# Power_MPU.net
KiCad netlist of a schematic drawn in Altium Designer
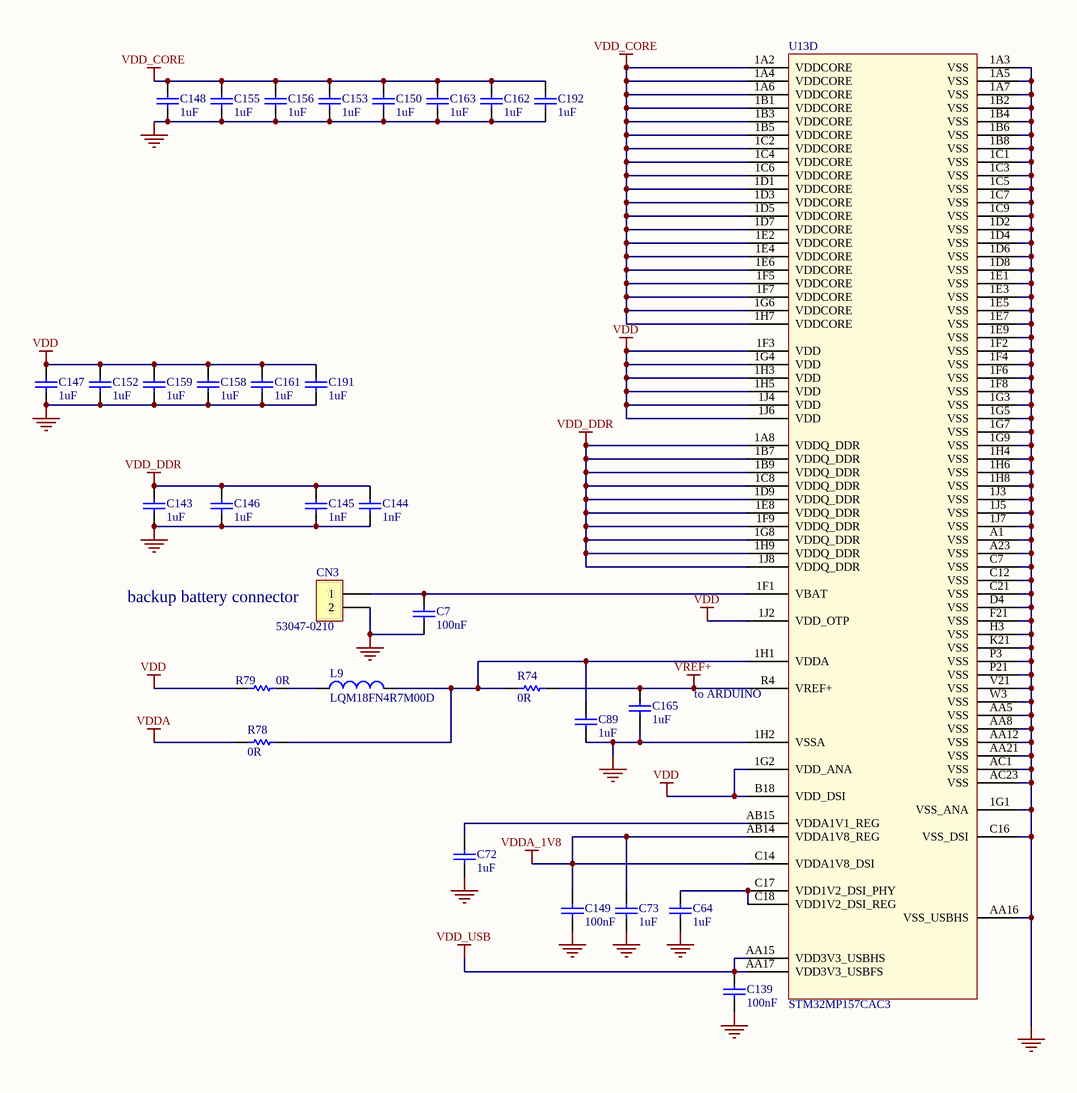
[diagram p0: Power_MPU.SchDoc]

(export (version "E")
  (design (tool "Eeschema 10.0.6"))
  (components
    (comp (ref "C7")
      (value "100nF")
      (footprint "C0402")
      (description "Capacitor,100nF,16V,X7R,10%,0402")
      (fields
        (field (name "INTERNAL_PART_NUMBER") "MCD-00006")
        (field (name "MANUFACTURER_PART_NUMBER") "CC0402KRX7R7BB104")
        (field (name "PROVIDED_BY") "SUBCO")
      )
      (libsource (lib "MCD_PARTS_database") (part "Capacitor"))
    )
    (comp (ref "C64")
      (value "1uF")
      (footprint "C0402")
      (description "Capacitor,1uF,6V3,X5R,10%,0402")
      (fields
        (field (name "INTERNAL_PART_NUMBER") "MCD-00095")
        (field (name "MANUFACTURER_PART_NUMBER") "GRM155R61E105KA12")
        (field (name "PROVIDED_BY") "SUBCO")
      )
      (libsource (lib "MCD_PARTS_database") (part "Capacitor"))
    )
    (comp (ref "C72")
      (value "1uF")
      (footprint "C0402")
      (description "Capacitor,1uF,6V3,X5R,10%,0402")
      (fields
        (field (name "INTERNAL_PART_NUMBER") "MCD-00095")
        (field (name "MANUFACTURER_PART_NUMBER") "GRM155R61E105KA12")
        (field (name "PROVIDED_BY") "SUBCO")
      )
      (libsource (lib "MCD_PARTS_database") (part "Capacitor"))
    )
    (comp (ref "C73")
      (value "1uF")
      (footprint "C0402")
      (description "Capacitor,1uF,6V3,X5R,10%,0402")
      (fields
        (field (name "INTERNAL_PART_NUMBER") "MCD-00095")
        (field (name "MANUFACTURER_PART_NUMBER") "GRM155R61E105KA12")
        (field (name "PROVIDED_BY") "SUBCO")
      )
      (libsource (lib "MCD_PARTS_database") (part "Capacitor"))
    )
    (comp (ref "C89")
      (value "1uF")
      (footprint "C0402")
      (description "Capacitor,1uF,6V3,X5R,10%,0402")
      (fields
        (field (name "INTERNAL_PART_NUMBER") "MCD-00095")
        (field (name "MANUFACTURER_PART_NUMBER") "GRM155R61E105KA12")
        (field (name "PROVIDED_BY") "SUBCO")
      )
      (libsource (lib "MCD_PARTS_database") (part "Capacitor"))
    )
    (comp (ref "C139")
      (value "100nF")
      (footprint "C0402")
      (description "Capacitor,100nF,16V,X7R,10%,0402")
      (fields
        (field (name "INTERNAL_PART_NUMBER") "MCD-00006")
        (field (name "MANUFACTURER_PART_NUMBER") "CC0402KRX7R7BB104")
        (field (name "PROVIDED_BY") "SUBCO")
      )
      (libsource (lib "MCD_PARTS_database") (part "Capacitor"))
    )
    (comp (ref "C143")
      (value "1uF")
      (footprint "C0402")
      (description "Capacitor,1uF,6V3,X5R,10%,0402")
      (fields
        (field (name "INTERNAL_PART_NUMBER") "MCD-00095")
        (field (name "MANUFACTURER_PART_NUMBER") "GRM155R61E105KA12")
        (field (name "PROVIDED_BY") "SUBCO")
      )
      (libsource (lib "MCD_PARTS_database") (part "Capacitor"))
    )
    (comp (ref "C144")
      (value "1nF")
      (footprint "C0402")
      (description "Capacitor,1nF,16V,X7R,10%,0402")
      (fields
        (field (name "INTERNAL_PART_NUMBER") "MCD-00198")
        (field (name "MANUFACTURER_PART_NUMBER") "CC0402KRX7R7BB102")
        (field (name "PROVIDED_BY") "SUBCO")
      )
      (libsource (lib "MCD_PARTS_database") (part "Capacitor"))
    )
    (comp (ref "C145")
      (value "1nF")
      (footprint "C0402")
      (description "Capacitor,1nF,16V,X7R,10%,0402")
      (fields
        (field (name "INTERNAL_PART_NUMBER") "MCD-00198")
        (field (name "MANUFACTURER_PART_NUMBER") "CC0402KRX7R7BB102")
        (field (name "PROVIDED_BY") "SUBCO")
      )
      (libsource (lib "MCD_PARTS_database") (part "Capacitor"))
    )
    (comp (ref "C146")
      (value "1uF")
      (footprint "C0402")
      (description "Capacitor,1uF,6V3,X5R,10%,0402")
      (fields
        (field (name "INTERNAL_PART_NUMBER") "MCD-00095")
        (field (name "MANUFACTURER_PART_NUMBER") "GRM155R61E105KA12")
        (field (name "PROVIDED_BY") "SUBCO")
      )
      (libsource (lib "MCD_PARTS_database") (part "Capacitor"))
    )
    (comp (ref "C147")
      (value "1uF")
      (footprint "C0402")
      (description "Capacitor,1uF,6V3,X5R,10%,0402")
      (fields
        (field (name "INTERNAL_PART_NUMBER") "MCD-00095")
        (field (name "MANUFACTURER_PART_NUMBER") "GRM155R61E105KA12")
        (field (name "PROVIDED_BY") "SUBCO")
      )
      (libsource (lib "MCD_PARTS_database") (part "Capacitor"))
    )
    (comp (ref "C148")
      (value "1uF")
      (footprint "C0402")
      (description "Capacitor,1uF,6V3,X5R,10%,0402")
      (fields
        (field (name "INTERNAL_PART_NUMBER") "MCD-00095")
        (field (name "MANUFACTURER_PART_NUMBER") "GRM155R61E105KA12")
        (field (name "PROVIDED_BY") "SUBCO")
      )
      (libsource (lib "MCD_PARTS_database") (part "Capacitor"))
    )
    (comp (ref "C149")
      (value "100nF")
      (footprint "C0402")
      (description "Capacitor,100nF,16V,X7R,10%,0402")
      (fields
        (field (name "INTERNAL_PART_NUMBER") "MCD-00006")
        (field (name "MANUFACTURER_PART_NUMBER") "CC0402KRX7R7BB104")
        (field (name "PROVIDED_BY") "SUBCO")
      )
      (libsource (lib "MCD_PARTS_database") (part "Capacitor"))
    )
    (comp (ref "C150")
      (value "1uF")
      (footprint "C0402")
      (description "Capacitor,1uF,6V3,X5R,10%,0402")
      (fields
        (field (name "INTERNAL_PART_NUMBER") "MCD-00095")
        (field (name "MANUFACTURER_PART_NUMBER") "GRM155R61E105KA12")
        (field (name "PROVIDED_BY") "SUBCO")
      )
      (libsource (lib "MCD_PARTS_database") (part "Capacitor"))
    )
    (comp (ref "C152")
      (value "1uF")
      (footprint "C0402")
      (description "Capacitor,1uF,6V3,X5R,10%,0402")
      (fields
        (field (name "INTERNAL_PART_NUMBER") "MCD-00095")
        (field (name "MANUFACTURER_PART_NUMBER") "GRM155R61E105KA12")
        (field (name "PROVIDED_BY") "SUBCO")
      )
      (libsource (lib "MCD_PARTS_database") (part "Capacitor"))
    )
    (comp (ref "C153")
      (value "1uF")
      (footprint "C0402")
      (description "Capacitor,1uF,6V3,X5R,10%,0402")
      (fields
        (field (name "INTERNAL_PART_NUMBER") "MCD-00095")
        (field (name "MANUFACTURER_PART_NUMBER") "GRM155R61E105KA12")
        (field (name "PROVIDED_BY") "SUBCO")
      )
      (libsource (lib "MCD_PARTS_database") (part "Capacitor"))
    )
    (comp (ref "C155")
      (value "1uF")
      (footprint "C0402")
      (description "Capacitor,1uF,6V3,X5R,10%,0402")
      (fields
        (field (name "INTERNAL_PART_NUMBER") "MCD-00095")
        (field (name "MANUFACTURER_PART_NUMBER") "GRM155R61E105KA12")
        (field (name "PROVIDED_BY") "SUBCO")
      )
      (libsource (lib "MCD_PARTS_database") (part "Capacitor"))
    )
    (comp (ref "C156")
      (value "1uF")
      (footprint "C0402")
      (description "Capacitor,1uF,6V3,X5R,10%,0402")
      (fields
        (field (name "INTERNAL_PART_NUMBER") "MCD-00095")
        (field (name "MANUFACTURER_PART_NUMBER") "GRM155R61E105KA12")
        (field (name "PROVIDED_BY") "SUBCO")
      )
      (libsource (lib "MCD_PARTS_database") (part "Capacitor"))
    )
    (comp (ref "C158")
      (value "1uF")
      (footprint "C0402")
      (description "Capacitor,1uF,6V3,X5R,10%,0402")
      (fields
        (field (name "INTERNAL_PART_NUMBER") "MCD-00095")
        (field (name "MANUFACTURER_PART_NUMBER") "GRM155R61E105KA12")
        (field (name "PROVIDED_BY") "SUBCO")
      )
      (libsource (lib "MCD_PARTS_database") (part "Capacitor"))
    )
    (comp (ref "C159")
      (value "1uF")
      (footprint "C0402")
      (description "Capacitor,1uF,6V3,X5R,10%,0402")
      (fields
        (field (name "INTERNAL_PART_NUMBER") "MCD-00095")
        (field (name "MANUFACTURER_PART_NUMBER") "GRM155R61E105KA12")
        (field (name "PROVIDED_BY") "SUBCO")
      )
      (libsource (lib "MCD_PARTS_database") (part "Capacitor"))
    )
    (comp (ref "C161")
      (value "1uF")
      (footprint "C0402")
      (description "Capacitor,1uF,6V3,X5R,10%,0402")
      (fields
        (field (name "INTERNAL_PART_NUMBER") "MCD-00095")
        (field (name "MANUFACTURER_PART_NUMBER") "GRM155R61E105KA12")
        (field (name "PROVIDED_BY") "SUBCO")
      )
      (libsource (lib "MCD_PARTS_database") (part "Capacitor"))
    )
    (comp (ref "C162")
      (value "1uF")
      (footprint "C0402")
      (description "Capacitor,1uF,6V3,X5R,10%,0402")
      (fields
        (field (name "INTERNAL_PART_NUMBER") "MCD-00095")
        (field (name "MANUFACTURER_PART_NUMBER") "GRM155R61E105KA12")
        (field (name "PROVIDED_BY") "SUBCO")
      )
      (libsource (lib "MCD_PARTS_database") (part "Capacitor"))
    )
    (comp (ref "C163")
      (value "1uF")
      (footprint "C0402")
      (description "Capacitor,1uF,6V3,X5R,10%,0402")
      (fields
        (field (name "INTERNAL_PART_NUMBER") "MCD-00095")
        (field (name "MANUFACTURER_PART_NUMBER") "GRM155R61E105KA12")
        (field (name "PROVIDED_BY") "SUBCO")
      )
      (libsource (lib "MCD_PARTS_database") (part "Capacitor"))
    )
    (comp (ref "C165")
      (value "1uF")
      (footprint "C0402")
      (description "Capacitor,1uF,6V3,X5R,10%,0402")
      (fields
        (field (name "INTERNAL_PART_NUMBER") "MCD-00095")
        (field (name "MANUFACTURER_PART_NUMBER") "GRM155R61E105KA12")
        (field (name "PROVIDED_BY") "SUBCO")
      )
      (libsource (lib "MCD_PARTS_database") (part "Capacitor"))
    )
    (comp (ref "C191")
      (value "1uF")
      (footprint "C0402")
      (description "Capacitor,1uF,6V3,X5R,10%,0402")
      (fields
        (field (name "INTERNAL_PART_NUMBER") "MCD-00095")
        (field (name "MANUFACTURER_PART_NUMBER") "GRM155R61E105KA12")
        (field (name "PROVIDED_BY") "SUBCO")
      )
      (libsource (lib "MCD_PARTS_database") (part "Capacitor"))
    )
    (comp (ref "C192")
      (value "1uF")
      (footprint "C0402")
      (description "Capacitor,1uF,6V3,X5R,10%,0402")
      (fields
        (field (name "INTERNAL_PART_NUMBER") "MCD-00095")
        (field (name "MANUFACTURER_PART_NUMBER") "GRM155R61E105KA12")
        (field (name "PROVIDED_BY") "SUBCO")
      )
      (libsource (lib "MCD_PARTS_database") (part "Capacitor"))
    )
    (comp (ref "CN3")
      (value "53047-0210")
      (footprint "CON_MOLEX_53047-0210")
      (description "Header 2 circuits, 1.25mm Pitch ,  Vertical, with Friction Lock")
      (fields
        (field (name "INTERNAL_PART_NUMBER") "MCD-00655")
        (field (name "MANUFACTURER") "MOLEX")
        (field (name "PROVIDED_BY") "SUBCO")
      )
      (libsource (lib "MCD_PARTS_database") (part "Header 2x1"))
    )
    (comp (ref "L9")
      (value "LQM18FN4R7M00D")
      (footprint "L0603")
      (description "IND 4.7µH 20% 80mA 600mhom 0603")
      (fields
        (field (name "INTERNAL_PART_NUMBER") "MCD-01134")
        (field (name "MANUFACTURER") "MURATA")
        (field (name "PROVIDED_BY") "SUBCO")
      )
      (libsource (lib "MCD_PARTS_database") (part "LQM18FN4R7M00D"))
    )
    (comp (ref "R74")
      (value "0R")
      (footprint "R0402")
      (description "Resistor,0R,0402,5%,1/16W")
      (fields
        (field (name "INTERNAL_PART_NUMBER") "MCD-00052")
        (field (name "MANUFACTURER_PART_NUMBER") "RC0402JR-070RL")
        (field (name "PROVIDED_BY") "SUBCO")
      )
      (libsource (lib "MCD_PARTS_database") (part "Resistor"))
    )
    (comp (ref "R78")
      (value "0R")
      (footprint "R0402")
      (description "Resistor,0R,0402,5%,1/16W")
      (fields
        (field (name "INTERNAL_PART_NUMBER") "MCD-00052")
        (field (name "MANUFACTURER_PART_NUMBER") "RC0402JR-070RL")
        (field (name "PROVIDED_BY") "SUBCO")
      )
      (libsource (lib "MCD_PARTS_database") (part "Resistor"))
    )
    (comp (ref "R79")
      (value "0R")
      (footprint "R0402")
      (description "Resistor,0R,0402,5%,1/16W")
      (fields
        (field (name "INTERNAL_PART_NUMBER") "MCD-00052")
        (field (name "MANUFACTURER_PART_NUMBER") "RC0402JR-070RL")
        (field (name "PROVIDED_BY") "SUBCO")
      )
      (libsource (lib "MCD_PARTS_database") (part "Resistor"))
    )
    (comp (ref "U13")
      (value "STM32MP157CAC3")
      (footprint "ICC_TFBGA361_12X12_STM32MP157CAC3_P050-065")
      (description "MPU TFBGA12x12 secure boot+crypto")
      (fields
        (field (name "INTERNAL_PART_NUMBER") "MCD-00677")
        (field (name "MANUFACTURER") "STMICROELECTRONICS")
        (field (name "PROVIDED_BY") "SUBCO with ST control")
      )
      (libsource (lib "MCD_PARTS_database") (part "STM32MP157CAC3"))
    )
  )
  (nets
    (net (code "1") (name "GND") (class "Default")
      (node (ref "C139") (pin "1") (pinfunction "1_1") (pintype "passive"))
      (node (ref "C143") (pin "1") (pinfunction "1_1") (pintype "passive"))
      (node (ref "C144") (pin "1") (pinfunction "1_1") (pintype "passive"))
      (node (ref "C145") (pin "1") (pinfunction "1_1") (pintype "passive"))
      (node (ref "C146") (pin "1") (pinfunction "1_1") (pintype "passive"))
      (node (ref "C147") (pin "1") (pinfunction "1_1") (pintype "passive"))
      (node (ref "C148") (pin "1") (pinfunction "1_1") (pintype "passive"))
      (node (ref "C149") (pin "1") (pinfunction "1_1") (pintype "passive"))
      (node (ref "C150") (pin "1") (pinfunction "1_1") (pintype "passive"))
      (node (ref "C152") (pin "1") (pinfunction "1_1") (pintype "passive"))
      (node (ref "C153") (pin "1") (pinfunction "1_1") (pintype "passive"))
      (node (ref "C155") (pin "1") (pinfunction "1_1") (pintype "passive"))
      (node (ref "C156") (pin "1") (pinfunction "1_1") (pintype "passive"))
      (node (ref "C158") (pin "1") (pinfunction "1_1") (pintype "passive"))
      (node (ref "C159") (pin "1") (pinfunction "1_1") (pintype "passive"))
      (node (ref "C161") (pin "1") (pinfunction "1_1") (pintype "passive"))
      (node (ref "C162") (pin "1") (pinfunction "1_1") (pintype "passive"))
      (node (ref "C163") (pin "1") (pinfunction "1_1") (pintype "passive"))
      (node (ref "C165") (pin "1") (pinfunction "1_1") (pintype "passive"))
      (node (ref "C191") (pin "1") (pinfunction "1_1") (pintype "passive"))
      (node (ref "C192") (pin "1") (pinfunction "1_1") (pintype "passive"))
      (node (ref "C64") (pin "1") (pinfunction "1_1") (pintype "passive"))
      (node (ref "C7") (pin "1") (pinfunction "1_1") (pintype "passive"))
      (node (ref "C72") (pin "1") (pinfunction "1_1") (pintype "passive"))
      (node (ref "C73") (pin "1") (pinfunction "1_1") (pintype "passive"))
      (node (ref "C89") (pin "1") (pinfunction "1_1") (pintype "passive"))
      (node (ref "CN3") (pin "2") (pinfunction "2_2") (pintype "passive"))
      (node (ref "U13") (pin "1A3") (pinfunction "VSS_1A3") (pintype "passive"))
      (node (ref "U13") (pin "1A5") (pinfunction "VSS_1A5") (pintype "passive"))
      (node (ref "U13") (pin "1A7") (pinfunction "VSS_1A7") (pintype "passive"))
      (node (ref "U13") (pin "1B2") (pinfunction "VSS_1B2") (pintype "passive"))
      (node (ref "U13") (pin "1B4") (pinfunction "VSS_1B4") (pintype "passive"))
      (node (ref "U13") (pin "1B6") (pinfunction "VSS_1B6") (pintype "passive"))
      (node (ref "U13") (pin "1B8") (pinfunction "VSS_1B8") (pintype "passive"))
      (node (ref "U13") (pin "1C1") (pinfunction "VSS_1C1") (pintype "passive"))
      (node (ref "U13") (pin "1C3") (pinfunction "VSS_1C3") (pintype "passive"))
      (node (ref "U13") (pin "1C5") (pinfunction "VSS_1C5") (pintype "passive"))
      (node (ref "U13") (pin "1C7") (pinfunction "VSS_1C7") (pintype "passive"))
      (node (ref "U13") (pin "1C9") (pinfunction "VSS_1C9") (pintype "passive"))
      (node (ref "U13") (pin "1D2") (pinfunction "VSS_1D2") (pintype "passive"))
      (node (ref "U13") (pin "1D4") (pinfunction "VSS_1D4") (pintype "passive"))
      (node (ref "U13") (pin "1D6") (pinfunction "VSS_1D6") (pintype "passive"))
      (node (ref "U13") (pin "1D8") (pinfunction "VSS_1D8") (pintype "passive"))
      (node (ref "U13") (pin "1E1") (pinfunction "VSS_1E1") (pintype "passive"))
      (node (ref "U13") (pin "1E3") (pinfunction "VSS_1E3") (pintype "passive"))
      (node (ref "U13") (pin "1E5") (pinfunction "VSS_1E5") (pintype "passive"))
      (node (ref "U13") (pin "1E7") (pinfunction "VSS_1E7") (pintype "passive"))
      (node (ref "U13") (pin "1E9") (pinfunction "VSS_1E9") (pintype "passive"))
      (node (ref "U13") (pin "1F2") (pinfunction "VSS_1F2") (pintype "passive"))
      (node (ref "U13") (pin "1F4") (pinfunction "VSS_1F4") (pintype "passive"))
      (node (ref "U13") (pin "1F6") (pinfunction "VSS_1F6") (pintype "passive"))
      (node (ref "U13") (pin "1F8") (pinfunction "VSS_1F8") (pintype "passive"))
      (node (ref "U13") (pin "1G1") (pinfunction "VSS_ANA_1G1") (pintype "passive"))
      (node (ref "U13") (pin "1G3") (pinfunction "VSS_1G3") (pintype "passive"))
      (node (ref "U13") (pin "1G5") (pinfunction "VSS_1G5") (pintype "passive"))
      (node (ref "U13") (pin "1G7") (pinfunction "VSS_1G7") (pintype "passive"))
      (node (ref "U13") (pin "1G9") (pinfunction "VSS_1G9") (pintype "passive"))
      (node (ref "U13") (pin "1H2") (pinfunction "VSSA_1H2") (pintype "passive"))
      (node (ref "U13") (pin "1H4") (pinfunction "VSS_1H4") (pintype "passive"))
      (node (ref "U13") (pin "1H6") (pinfunction "VSS_1H6") (pintype "passive"))
      (node (ref "U13") (pin "1H8") (pinfunction "VSS_1H8") (pintype "passive"))
      (node (ref "U13") (pin "1J3") (pinfunction "VSS_1J3") (pintype "passive"))
      (node (ref "U13") (pin "1J5") (pinfunction "VSS_1J5") (pintype "passive"))
      (node (ref "U13") (pin "1J7") (pinfunction "VSS_1J7") (pintype "passive"))
      (node (ref "U13") (pin "A1") (pinfunction "VSS_A1") (pintype "passive"))
      (node (ref "U13") (pin "A23") (pinfunction "VSS_A23") (pintype "passive"))
      (node (ref "U13") (pin "AA12") (pinfunction "VSS_AA12") (pintype "passive"))
      (node (ref "U13") (pin "AA16") (pinfunction "VSS_USBHS_AA16") (pintype "passive"))
      (node (ref "U13") (pin "AA21") (pinfunction "VSS_AA21") (pintype "passive"))
      (node (ref "U13") (pin "AA5") (pinfunction "VSS_AA5") (pintype "passive"))
      (node (ref "U13") (pin "AA8") (pinfunction "VSS_AA8") (pintype "passive"))
      (node (ref "U13") (pin "AC1") (pinfunction "VSS_AC1") (pintype "passive"))
      (node (ref "U13") (pin "AC23") (pinfunction "VSS_AC23") (pintype "passive"))
      (node (ref "U13") (pin "C12") (pinfunction "VSS_C12") (pintype "passive"))
      (node (ref "U13") (pin "C16") (pinfunction "VSS_DSI_C16") (pintype "passive"))
      (node (ref "U13") (pin "C21") (pinfunction "VSS_C21") (pintype "passive"))
      (node (ref "U13") (pin "C7") (pinfunction "VSS_C7") (pintype "passive"))
      (node (ref "U13") (pin "D4") (pinfunction "VSS_D4") (pintype "passive"))
      (node (ref "U13") (pin "F21") (pinfunction "VSS_F21") (pintype "passive"))
      (node (ref "U13") (pin "H3") (pinfunction "VSS_H3") (pintype "passive"))
      (node (ref "U13") (pin "K21") (pinfunction "VSS_K21") (pintype "passive"))
      (node (ref "U13") (pin "P21") (pinfunction "VSS_P21") (pintype "passive"))
      (node (ref "U13") (pin "P3") (pinfunction "VSS_P3") (pintype "passive"))
      (node (ref "U13") (pin "V21") (pinfunction "VSS_V21") (pintype "passive"))
      (node (ref "U13") (pin "W3") (pinfunction "VSS_W3") (pintype "passive"))
    )
    (net (code "2") (name "Net-(L9-Pad1)") (class "Default")
      (node (ref "L9") (pin "1") (pinfunction "1_1") (pintype "passive"))
      (node (ref "R79") (pin "2") (pinfunction "2_2") (pintype "passive"))
    )
    (net (code "3") (name "Net-(U13D-VBAT)") (class "Default")
      (node (ref "C7") (pin "2") (pinfunction "2_2") (pintype "passive"))
      (node (ref "CN3") (pin "1") (pinfunction "1_1") (pintype "passive"))
      (node (ref "U13") (pin "1F1") (pinfunction "VBAT_1F1") (pintype "passive"))
    )
    (net (code "4") (name "Net-(U13D-VDD1V2_DSI_PHY)") (class "Default")
      (node (ref "C64") (pin "2") (pinfunction "2_2") (pintype "passive"))
      (node (ref "U13") (pin "C17") (pinfunction "VDD1V2_DSI_PHY_C17") (pintype "passive"))
      (node (ref "U13") (pin "C18") (pinfunction "VDD1V2_DSI_REG_C18") (pintype "passive"))
    )
    (net (code "5") (name "Net-(U13D-VDDA)") (class "Default")
      (node (ref "C89") (pin "2") (pinfunction "2_2") (pintype "passive"))
      (node (ref "L9") (pin "2") (pinfunction "2_2") (pintype "passive"))
      (node (ref "R74") (pin "1") (pinfunction "1_1") (pintype "passive"))
      (node (ref "R78") (pin "2") (pinfunction "2_2") (pintype "passive"))
      (node (ref "U13") (pin "1H1") (pinfunction "VDDA_1H1") (pintype "passive"))
    )
    (net (code "6") (name "Net-(U13D-VDDA1V1_REG)") (class "Default")
      (node (ref "C72") (pin "2") (pinfunction "2_2") (pintype "passive"))
      (node (ref "U13") (pin "AB15") (pinfunction "VDDA1V1_REG_AB15") (pintype "passive"))
    )
    (net (code "7") (name "VDD") (class "Default")
      (node (ref "C147") (pin "2") (pinfunction "2_2") (pintype "passive"))
      (node (ref "C152") (pin "2") (pinfunction "2_2") (pintype "passive"))
      (node (ref "C158") (pin "2") (pinfunction "2_2") (pintype "passive"))
      (node (ref "C159") (pin "2") (pinfunction "2_2") (pintype "passive"))
      (node (ref "C161") (pin "2") (pinfunction "2_2") (pintype "passive"))
      (node (ref "C191") (pin "2") (pinfunction "2_2") (pintype "passive"))
      (node (ref "R79") (pin "1") (pinfunction "1_1") (pintype "passive"))
      (node (ref "U13") (pin "1F3") (pinfunction "VDD_1F3") (pintype "passive"))
      (node (ref "U13") (pin "1G2") (pinfunction "VDD_ANA_1G2") (pintype "passive"))
      (node (ref "U13") (pin "1G4") (pinfunction "VDD_1G4") (pintype "passive"))
      (node (ref "U13") (pin "1H3") (pinfunction "VDD_1H3") (pintype "passive"))
      (node (ref "U13") (pin "1H5") (pinfunction "VDD_1H5") (pintype "passive"))
      (node (ref "U13") (pin "1J2") (pinfunction "VDD_OTP_1J2") (pintype "passive"))
      (node (ref "U13") (pin "1J4") (pinfunction "VDD_1J4") (pintype "passive"))
      (node (ref "U13") (pin "1J6") (pinfunction "VDD_1J6") (pintype "passive"))
      (node (ref "U13") (pin "B18") (pinfunction "VDD_DSI_B18") (pintype "passive"))
    )
    (net (code "8") (name "VDDA") (class "Default")
      (node (ref "R78") (pin "1") (pinfunction "1_1") (pintype "passive"))
    )
    (net (code "9") (name "VDDA_1V8") (class "Default")
      (node (ref "C149") (pin "2") (pinfunction "2_2") (pintype "passive"))
      (node (ref "C73") (pin "2") (pinfunction "2_2") (pintype "passive"))
      (node (ref "U13") (pin "AB14") (pinfunction "VDDA1V8_REG_AB14") (pintype "passive"))
      (node (ref "U13") (pin "C14") (pinfunction "VDDA1V8_DSI_C14") (pintype "passive"))
    )
    (net (code "10") (name "VDD_CORE") (class "Default")
      (node (ref "C148") (pin "2") (pinfunction "2_2") (pintype "passive"))
      (node (ref "C150") (pin "2") (pinfunction "2_2") (pintype "passive"))
      (node (ref "C153") (pin "2") (pinfunction "2_2") (pintype "passive"))
      (node (ref "C155") (pin "2") (pinfunction "2_2") (pintype "passive"))
      (node (ref "C156") (pin "2") (pinfunction "2_2") (pintype "passive"))
      (node (ref "C162") (pin "2") (pinfunction "2_2") (pintype "passive"))
      (node (ref "C163") (pin "2") (pinfunction "2_2") (pintype "passive"))
      (node (ref "C192") (pin "2") (pinfunction "2_2") (pintype "passive"))
      (node (ref "U13") (pin "1A2") (pinfunction "VDDCORE_1A2") (pintype "passive"))
      (node (ref "U13") (pin "1A4") (pinfunction "VDDCORE_1A4") (pintype "passive"))
      (node (ref "U13") (pin "1A6") (pinfunction "VDDCORE_1A6") (pintype "passive"))
      (node (ref "U13") (pin "1B1") (pinfunction "VDDCORE_1B1") (pintype "passive"))
      (node (ref "U13") (pin "1B3") (pinfunction "VDDCORE_1B3") (pintype "passive"))
      (node (ref "U13") (pin "1B5") (pinfunction "VDDCORE_1B5") (pintype "passive"))
      (node (ref "U13") (pin "1C2") (pinfunction "VDDCORE_1C2") (pintype "passive"))
      (node (ref "U13") (pin "1C4") (pinfunction "VDDCORE_1C4") (pintype "passive"))
      (node (ref "U13") (pin "1C6") (pinfunction "VDDCORE_1C6") (pintype "passive"))
      (node (ref "U13") (pin "1D1") (pinfunction "VDDCORE_1D1") (pintype "passive"))
      (node (ref "U13") (pin "1D3") (pinfunction "VDDCORE_1D3") (pintype "passive"))
      (node (ref "U13") (pin "1D5") (pinfunction "VDDCORE_1D5") (pintype "passive"))
      (node (ref "U13") (pin "1D7") (pinfunction "VDDCORE_1D7") (pintype "passive"))
      (node (ref "U13") (pin "1E2") (pinfunction "VDDCORE_1E2") (pintype "passive"))
      (node (ref "U13") (pin "1E4") (pinfunction "VDDCORE_1E4") (pintype "passive"))
      (node (ref "U13") (pin "1E6") (pinfunction "VDDCORE_1E6") (pintype "passive"))
      (node (ref "U13") (pin "1F5") (pinfunction "VDDCORE_1F5") (pintype "passive"))
      (node (ref "U13") (pin "1F7") (pinfunction "VDDCORE_1F7") (pintype "passive"))
      (node (ref "U13") (pin "1G6") (pinfunction "VDDCORE_1G6") (pintype "passive"))
      (node (ref "U13") (pin "1H7") (pinfunction "VDDCORE_1H7") (pintype "passive"))
    )
    (net (code "11") (name "VDD_DDR") (class "Default")
      (node (ref "C143") (pin "2") (pinfunction "2_2") (pintype "passive"))
      (node (ref "C144") (pin "2") (pinfunction "2_2") (pintype "passive"))
      (node (ref "C145") (pin "2") (pinfunction "2_2") (pintype "passive"))
      (node (ref "C146") (pin "2") (pinfunction "2_2") (pintype "passive"))
      (node (ref "U13") (pin "1A8") (pinfunction "VDDQ_DDR_1A8") (pintype "passive"))
      (node (ref "U13") (pin "1B7") (pinfunction "VDDQ_DDR_1B7") (pintype "passive"))
      (node (ref "U13") (pin "1B9") (pinfunction "VDDQ_DDR_1B9") (pintype "passive"))
      (node (ref "U13") (pin "1C8") (pinfunction "VDDQ_DDR_1C8") (pintype "passive"))
      (node (ref "U13") (pin "1D9") (pinfunction "VDDQ_DDR_1D9") (pintype "passive"))
      (node (ref "U13") (pin "1E8") (pinfunction "VDDQ_DDR_1E8") (pintype "passive"))
      (node (ref "U13") (pin "1F9") (pinfunction "VDDQ_DDR_1F9") (pintype "passive"))
      (node (ref "U13") (pin "1G8") (pinfunction "VDDQ_DDR_1G8") (pintype "passive"))
      (node (ref "U13") (pin "1H9") (pinfunction "VDDQ_DDR_1H9") (pintype "passive"))
      (node (ref "U13") (pin "1J8") (pinfunction "VDDQ_DDR_1J8") (pintype "passive"))
    )
    (net (code "12") (name "VDD_USB") (class "Default")
      (node (ref "C139") (pin "2") (pinfunction "2_2") (pintype "passive"))
      (node (ref "U13") (pin "AA15") (pinfunction "VDD3V3_USBHS_AA15") (pintype "passive"))
      (node (ref "U13") (pin "AA17") (pinfunction "VDD3V3_USBFS_AA17") (pintype "passive"))
    )
    (net (code "13") (name "VREF+") (class "Default")
      (node (ref "C165") (pin "2") (pinfunction "2_2") (pintype "passive"))
      (node (ref "R74") (pin "2") (pinfunction "2_2") (pintype "passive"))
      (node (ref "U13") (pin "R4") (pinfunction "VREF+_R4") (pintype "passive"))
    )
  )
)
